# Leg.net
KiCad netlist of a schematic drawn in Altium Designer
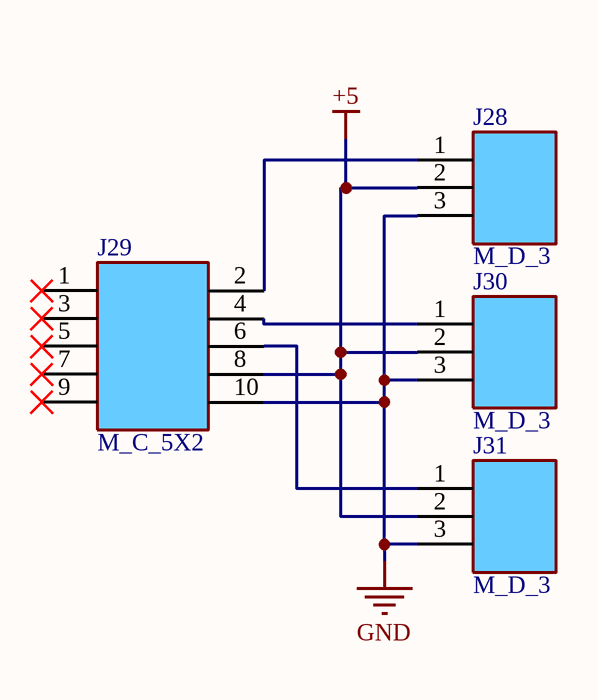
[diagram p0: Leg.SchDoc]

(export (version "E")
  (design (tool "Eeschema 10.0.6"))
  (components
    (comp (ref "J28")
      (value "BARRETTE 3 CONTACTS 1 RANGEE MALE DROITE")
      (footprint "BARRETTE_3_M_D")
      (fields (field (name "TYPE") "M_D_3"))
      (libsource (lib "connecteurs") (part "BARRETTE_3 CONTACTS_1 RANGEE_MALE_DROITE"))
    )
    (comp (ref "J29")
      (value "BARRETTE_5 CONTACTS_2 RANGEES_MALE_COUDEE")
      (footprint "BARRETTE_5X2_M_C")
      (description "BARRETTE 5 CONTACTS 2 RANGEES MALE COUDEE")
      (fields (field (name "TYPE") "M_C_5X2"))
      (libsource (lib "connecteurs") (part "BARRETTE_5 CONTACTS_2 RANGEES_MALE_COUDEE"))
    )
    (comp (ref "J30")
      (value "BARRETTE 3 CONTACTS 1 RANGEE MALE DROITE")
      (footprint "BARRETTE_3_M_D")
      (fields (field (name "TYPE") "M_D_3"))
      (libsource (lib "connecteurs") (part "BARRETTE_3 CONTACTS_1 RANGEE_MALE_DROITE"))
    )
    (comp (ref "J31")
      (value "BARRETTE 3 CONTACTS 1 RANGEE MALE DROITE")
      (footprint "BARRETTE_3_M_D")
      (fields (field (name "TYPE") "M_D_3"))
      (libsource (lib "connecteurs") (part "BARRETTE_3 CONTACTS_1 RANGEE_MALE_DROITE"))
    )
  )
  (nets
    (net (code "1") (name "+5") (class "Default")
      (node (ref "J28") (pin "2") (pinfunction "2_2") (pintype "passive"))
      (node (ref "J29") (pin "8") (pinfunction "8_8") (pintype "passive"))
      (node (ref "J30") (pin "2") (pinfunction "2_2") (pintype "passive"))
      (node (ref "J31") (pin "2") (pinfunction "2_2") (pintype "passive"))
    )
    (net (code "2") (name "GND") (class "Default")
      (node (ref "J28") (pin "3") (pinfunction "3_3") (pintype "passive"))
      (node (ref "J29") (pin "10") (pinfunction "10_10") (pintype "passive"))
      (node (ref "J30") (pin "3") (pinfunction "3_3") (pintype "passive"))
      (node (ref "J31") (pin "3") (pinfunction "3_3") (pintype "passive"))
    )
    (net (code "3") (name "Net-(J28-Pad1)") (class "Default")
      (node (ref "J28") (pin "1") (pinfunction "1_1") (pintype "passive"))
      (node (ref "J29") (pin "2") (pinfunction "2_2") (pintype "passive"))
    )
    (net (code "4") (name "Net-(J29-Pad4)") (class "Default")
      (node (ref "J29") (pin "4") (pinfunction "4_4") (pintype "passive"))
      (node (ref "J30") (pin "1") (pinfunction "1_1") (pintype "passive"))
    )
    (net (code "5") (name "Net-(J29-Pad6)") (class "Default")
      (node (ref "J29") (pin "6") (pinfunction "6_6") (pintype "passive"))
      (node (ref "J31") (pin "1") (pinfunction "1_1") (pintype "passive"))
    )
    (net (code "6") (name "unconnected-(J29-Pad1)") (class "Default")
      (node (ref "J29") (pin "1") (pinfunction "1_1") (pintype "passive+no_connect"))
    )
    (net (code "7") (name "unconnected-(J29-Pad3)") (class "Default")
      (node (ref "J29") (pin "3") (pinfunction "3_3") (pintype "passive+no_connect"))
    )
    (net (code "8") (name "unconnected-(J29-Pad5)") (class "Default")
      (node (ref "J29") (pin "5") (pinfunction "5_5") (pintype "passive+no_connect"))
    )
    (net (code "9") (name "unconnected-(J29-Pad7)") (class "Default")
      (node (ref "J29") (pin "7") (pinfunction "7_7") (pintype "passive+no_connect"))
    )
    (net (code "10") (name "unconnected-(J29-Pad9)") (class "Default")
      (node (ref "J29") (pin "9") (pinfunction "9_9") (pintype "passive+no_connect"))
    )
  )
)
